# SCHMITT_LED.net
KiCad netlist of a schematic drawn in Altium Designer
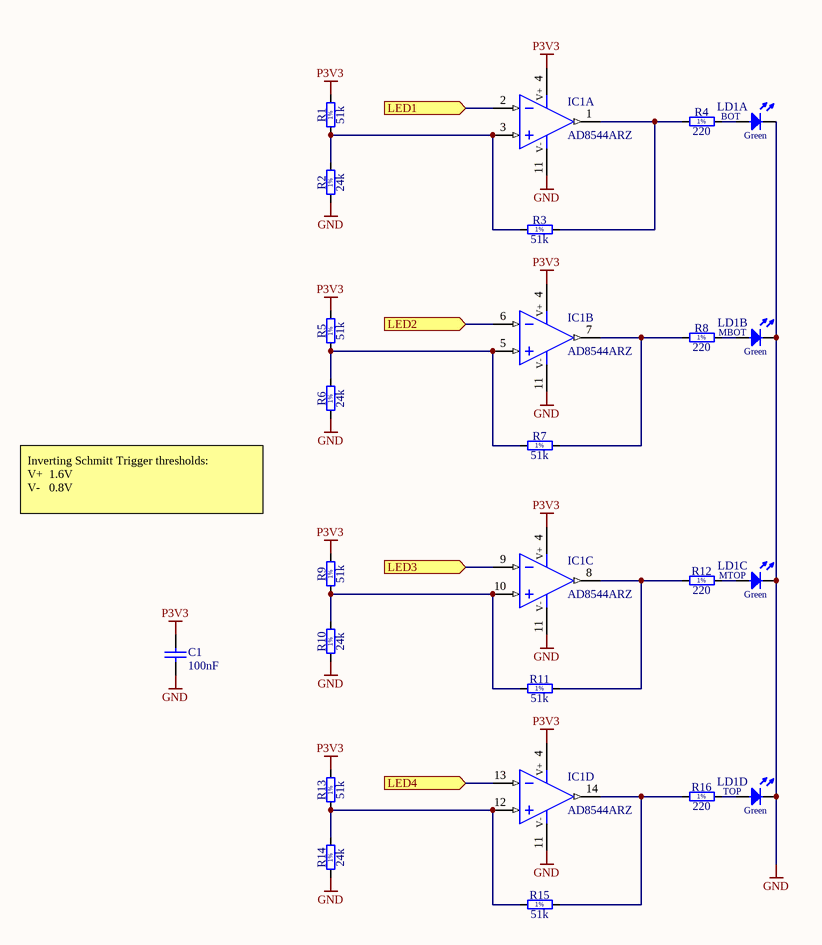
[diagram p0: SCHMITT_LED.SchDoc]

(export (version "E")
  (design (tool "Eeschema 10.0.6"))
  (components
    (comp (ref "C1")
      (value "100nF")
      (footprint "C0402C104K4RACTU")
      (description "Capacitor; Ceramic; Cap; .100uF; Tol 10%; SMT; Vol-Rtg 16V; X7R; Tape and Reel")
      (fields (field (name "TOLERANCE") "10%"))
      (libsource (lib "CapacitorLibrary") (part "C0402C104K4RACTU"))
    )
    (comp (ref "IC1")
      (value "AD8544ARZ")
      (footprint "SOIC127P600X175-14N")
      (description "Quad Operational Amplifier")
      (fields (field (name "MANUFACTURER") "ANALOG DEVICES") (field (name "AUTHOR") "CERN DEM JLC"))
      (libsource (lib "ICs And Semiconductors") (part "Operational Amplifier x4 Type1"))
    )
    (comp (ref "LD1")
      (value "Green")
      (footprint "LED_BIVAR_H485CGDL")
      (description "LED x4 Green 1C2A-BOT_3C4A_5C6A_7C8A-TOP")
      (fields
        (field (name "PART NUMBER") "LED_BIVAR_H485CGDL")
        (field (name "MANUFACTURER") "BIVAR")
        (field (name "AUTHOR") "CERN DEM JLC")
      )
      (libsource (lib "ICs And Semiconductors") (part "LED x4 Green 1C2A-BOT_3C4A_5C6A_7C8A-TOP"))
    )
    (comp (ref "R1")
      (value "51k")
      (footprint "RESC1608X55N")
      (description "Resistor - 1%")
      (fields
        (field (name "PART NUMBER") "R0603_51K_1%_0.1W_100PPM")
        (field (name "POWER") "0.1W")
        (field (name "AUTHOR") "CERN DEM JLC")
      )
      (libsource (lib "Resistors") (part "Resistor - 1%"))
    )
    (comp (ref "R2")
      (value "24k")
      (footprint "RESC1608X55N")
      (description "Resistor - 1%")
      (fields
        (field (name "PART NUMBER") "R0603_24K_1%_0.1W_100PPM")
        (field (name "POWER") "0.1W")
        (field (name "AUTHOR") "CERN DEM JLC")
      )
      (libsource (lib "Resistors") (part "Resistor - 1%"))
    )
    (comp (ref "R3")
      (value "51k")
      (footprint "RESC1608X55N")
      (description "Resistor - 1%")
      (fields
        (field (name "PART NUMBER") "R0603_51K_1%_0.1W_100PPM")
        (field (name "POWER") "0.1W")
        (field (name "AUTHOR") "CERN DEM JLC")
      )
      (libsource (lib "Resistors") (part "Resistor - 1%"))
    )
    (comp (ref "R4")
      (value "220")
      (footprint "RESC1608X55N")
      (description "Resistor - 1%")
      (fields
        (field (name "PART NUMBER") "R0603_220R_1%_0.1W_100PPM")
        (field (name "POWER") "0.1W")
        (field (name "AUTHOR") "CERN DEM JLC")
      )
      (libsource (lib "Resistors") (part "Resistor - 1%"))
    )
    (comp (ref "R5")
      (value "51k")
      (footprint "RESC1608X55N")
      (description "Resistor - 1%")
      (fields
        (field (name "PART NUMBER") "R0603_51K_1%_0.1W_100PPM")
        (field (name "POWER") "0.1W")
        (field (name "AUTHOR") "CERN DEM JLC")
      )
      (libsource (lib "Resistors") (part "Resistor - 1%"))
    )
    (comp (ref "R6")
      (value "24k")
      (footprint "RESC1608X55N")
      (description "Resistor - 1%")
      (fields
        (field (name "PART NUMBER") "R0603_24K_1%_0.1W_100PPM")
        (field (name "POWER") "0.1W")
        (field (name "AUTHOR") "CERN DEM JLC")
      )
      (libsource (lib "Resistors") (part "Resistor - 1%"))
    )
    (comp (ref "R7")
      (value "51k")
      (footprint "RESC1608X55N")
      (description "Resistor - 1%")
      (fields
        (field (name "PART NUMBER") "R0603_51K_1%_0.1W_100PPM")
        (field (name "POWER") "0.1W")
        (field (name "AUTHOR") "CERN DEM JLC")
      )
      (libsource (lib "Resistors") (part "Resistor - 1%"))
    )
    (comp (ref "R8")
      (value "220")
      (footprint "RESC1608X55N")
      (description "Resistor - 1%")
      (fields
        (field (name "PART NUMBER") "R0603_220R_1%_0.1W_100PPM")
        (field (name "POWER") "0.1W")
        (field (name "AUTHOR") "CERN DEM JLC")
      )
      (libsource (lib "Resistors") (part "Resistor - 1%"))
    )
    (comp (ref "R9")
      (value "51k")
      (footprint "RESC1608X55N")
      (description "Resistor - 1%")
      (fields
        (field (name "PART NUMBER") "R0603_51K_1%_0.1W_100PPM")
        (field (name "POWER") "0.1W")
        (field (name "AUTHOR") "CERN DEM JLC")
      )
      (libsource (lib "Resistors") (part "Resistor - 1%"))
    )
    (comp (ref "R10")
      (value "24k")
      (footprint "RESC1608X55N")
      (description "Resistor - 1%")
      (fields
        (field (name "PART NUMBER") "R0603_24K_1%_0.1W_100PPM")
        (field (name "POWER") "0.1W")
        (field (name "AUTHOR") "CERN DEM JLC")
      )
      (libsource (lib "Resistors") (part "Resistor - 1%"))
    )
    (comp (ref "R11")
      (value "51k")
      (footprint "RESC1608X55N")
      (description "Resistor - 1%")
      (fields
        (field (name "PART NUMBER") "R0603_51K_1%_0.1W_100PPM")
        (field (name "POWER") "0.1W")
        (field (name "AUTHOR") "CERN DEM JLC")
      )
      (libsource (lib "Resistors") (part "Resistor - 1%"))
    )
    (comp (ref "R12")
      (value "220")
      (footprint "RESC1608X55N")
      (description "Resistor - 1%")
      (fields
        (field (name "PART NUMBER") "R0603_220R_1%_0.1W_100PPM")
        (field (name "POWER") "0.1W")
        (field (name "AUTHOR") "CERN DEM JLC")
      )
      (libsource (lib "Resistors") (part "Resistor - 1%"))
    )
    (comp (ref "R13")
      (value "51k")
      (footprint "RESC1608X55N")
      (description "Resistor - 1%")
      (fields
        (field (name "PART NUMBER") "R0603_51K_1%_0.1W_100PPM")
        (field (name "POWER") "0.1W")
        (field (name "AUTHOR") "CERN DEM JLC")
      )
      (libsource (lib "Resistors") (part "Resistor - 1%"))
    )
    (comp (ref "R14")
      (value "24k")
      (footprint "RESC1608X55N")
      (description "Resistor - 1%")
      (fields
        (field (name "PART NUMBER") "R0603_24K_1%_0.1W_100PPM")
        (field (name "POWER") "0.1W")
        (field (name "AUTHOR") "CERN DEM JLC")
      )
      (libsource (lib "Resistors") (part "Resistor - 1%"))
    )
    (comp (ref "R15")
      (value "51k")
      (footprint "RESC1608X55N")
      (description "Resistor - 1%")
      (fields
        (field (name "PART NUMBER") "R0603_51K_1%_0.1W_100PPM")
        (field (name "POWER") "0.1W")
        (field (name "AUTHOR") "CERN DEM JLC")
      )
      (libsource (lib "Resistors") (part "Resistor - 1%"))
    )
    (comp (ref "R16")
      (value "220")
      (footprint "RESC1608X55N")
      (description "Resistor - 1%")
      (fields
        (field (name "PART NUMBER") "R0603_220R_1%_0.1W_100PPM")
        (field (name "POWER") "0.1W")
        (field (name "AUTHOR") "CERN DEM JLC")
      )
      (libsource (lib "Resistors") (part "Resistor - 1%"))
    )
  )
  (nets
    (net (code "1") (name "/LED1") (class "Default")
      (node (ref "IC1") (pin "2") (pinfunction "IN-_2") (pintype "input"))
    )
    (net (code "2") (name "/LED2") (class "Default")
      (node (ref "IC1") (pin "6") (pinfunction "IN-_6") (pintype "input"))
    )
    (net (code "3") (name "/LED3") (class "Default")
      (node (ref "IC1") (pin "9") (pinfunction "IN-_9") (pintype "input"))
    )
    (net (code "4") (name "/LED4") (class "Default")
      (node (ref "IC1") (pin "13") (pinfunction "IN-_13") (pintype "input"))
    )
    (net (code "5") (name "GND") (class "Default")
      (node (ref "C1") (pin "1") (pinfunction "1_1") (pintype "passive"))
      (node (ref "IC1") (pin "11") (pinfunction "V-_11") (pintype "power_in"))
      (node (ref "LD1") (pin "1") (pinfunction "C_1") (pintype "passive"))
      (node (ref "LD1") (pin "3") (pinfunction "C_3") (pintype "passive"))
      (node (ref "LD1") (pin "5") (pinfunction "C_5") (pintype "passive"))
      (node (ref "LD1") (pin "7") (pinfunction "C_7") (pintype "passive"))
      (node (ref "R10") (pin "1") (pinfunction "1_1") (pintype "passive"))
      (node (ref "R14") (pin "1") (pinfunction "1_1") (pintype "passive"))
      (node (ref "R2") (pin "1") (pinfunction "1_1") (pintype "passive"))
      (node (ref "R6") (pin "1") (pinfunction "1_1") (pintype "passive"))
    )
    (net (code "6") (name "Net-(IC1A-IN+)") (class "Default")
      (node (ref "IC1") (pin "3") (pinfunction "IN+_3") (pintype "input"))
      (node (ref "R1") (pin "1") (pinfunction "1_1") (pintype "passive"))
      (node (ref "R2") (pin "2") (pinfunction "2_2") (pintype "passive"))
      (node (ref "R3") (pin "1") (pinfunction "1_1") (pintype "passive"))
    )
    (net (code "7") (name "Net-(IC1A-OUT)") (class "Default")
      (node (ref "IC1") (pin "1") (pinfunction "OUT_1") (pintype "output"))
      (node (ref "R3") (pin "2") (pinfunction "2_2") (pintype "passive"))
      (node (ref "R4") (pin "1") (pinfunction "1_1") (pintype "passive"))
    )
    (net (code "8") (name "Net-(IC1B-IN+)") (class "Default")
      (node (ref "IC1") (pin "5") (pinfunction "IN+_5") (pintype "input"))
      (node (ref "R5") (pin "1") (pinfunction "1_1") (pintype "passive"))
      (node (ref "R6") (pin "2") (pinfunction "2_2") (pintype "passive"))
      (node (ref "R7") (pin "1") (pinfunction "1_1") (pintype "passive"))
    )
    (net (code "9") (name "Net-(IC1B-OUT)") (class "Default")
      (node (ref "IC1") (pin "7") (pinfunction "OUT_7") (pintype "output"))
      (node (ref "R7") (pin "2") (pinfunction "2_2") (pintype "passive"))
      (node (ref "R8") (pin "1") (pinfunction "1_1") (pintype "passive"))
    )
    (net (code "10") (name "Net-(IC1C-IN+)") (class "Default")
      (node (ref "IC1") (pin "10") (pinfunction "IN+_10") (pintype "input"))
      (node (ref "R10") (pin "2") (pinfunction "2_2") (pintype "passive"))
      (node (ref "R11") (pin "1") (pinfunction "1_1") (pintype "passive"))
      (node (ref "R9") (pin "1") (pinfunction "1_1") (pintype "passive"))
    )
    (net (code "11") (name "Net-(IC1C-OUT)") (class "Default")
      (node (ref "IC1") (pin "8") (pinfunction "OUT_8") (pintype "output"))
      (node (ref "R11") (pin "2") (pinfunction "2_2") (pintype "passive"))
      (node (ref "R12") (pin "1") (pinfunction "1_1") (pintype "passive"))
    )
    (net (code "12") (name "Net-(IC1D-IN+)") (class "Default")
      (node (ref "IC1") (pin "12") (pinfunction "IN+_12") (pintype "input"))
      (node (ref "R13") (pin "1") (pinfunction "1_1") (pintype "passive"))
      (node (ref "R14") (pin "2") (pinfunction "2_2") (pintype "passive"))
      (node (ref "R15") (pin "1") (pinfunction "1_1") (pintype "passive"))
    )
    (net (code "13") (name "Net-(IC1D-OUT)") (class "Default")
      (node (ref "IC1") (pin "14") (pinfunction "OUT_14") (pintype "output"))
      (node (ref "R15") (pin "2") (pinfunction "2_2") (pintype "passive"))
      (node (ref "R16") (pin "1") (pinfunction "1_1") (pintype "passive"))
    )
    (net (code "14") (name "Net-(LD1A-A)") (class "Default")
      (node (ref "LD1") (pin "2") (pinfunction "A_2") (pintype "passive"))
      (node (ref "R4") (pin "2") (pinfunction "2_2") (pintype "passive"))
    )
    (net (code "15") (name "Net-(LD1B-A)") (class "Default")
      (node (ref "LD1") (pin "4") (pinfunction "A_4") (pintype "passive"))
      (node (ref "R8") (pin "2") (pinfunction "2_2") (pintype "passive"))
    )
    (net (code "16") (name "Net-(LD1C-A)") (class "Default")
      (node (ref "LD1") (pin "6") (pinfunction "A_6") (pintype "passive"))
      (node (ref "R12") (pin "2") (pinfunction "2_2") (pintype "passive"))
    )
    (net (code "17") (name "Net-(LD1D-A)") (class "Default")
      (node (ref "LD1") (pin "8") (pinfunction "A_8") (pintype "passive"))
      (node (ref "R16") (pin "2") (pinfunction "2_2") (pintype "passive"))
    )
    (net (code "18") (name "P3V3") (class "Default")
      (node (ref "C1") (pin "2") (pinfunction "2_2") (pintype "passive"))
      (node (ref "IC1") (pin "4") (pinfunction "V+_4") (pintype "power_in"))
      (node (ref "R1") (pin "2") (pinfunction "2_2") (pintype "passive"))
      (node (ref "R13") (pin "2") (pinfunction "2_2") (pintype "passive"))
      (node (ref "R5") (pin "2") (pinfunction "2_2") (pintype "passive"))
      (node (ref "R9") (pin "2") (pinfunction "2_2") (pintype "passive"))
    )
  )
)
